# Schematic_Light_Project.net
KiCad netlist of a schematic drawn in EAGLE
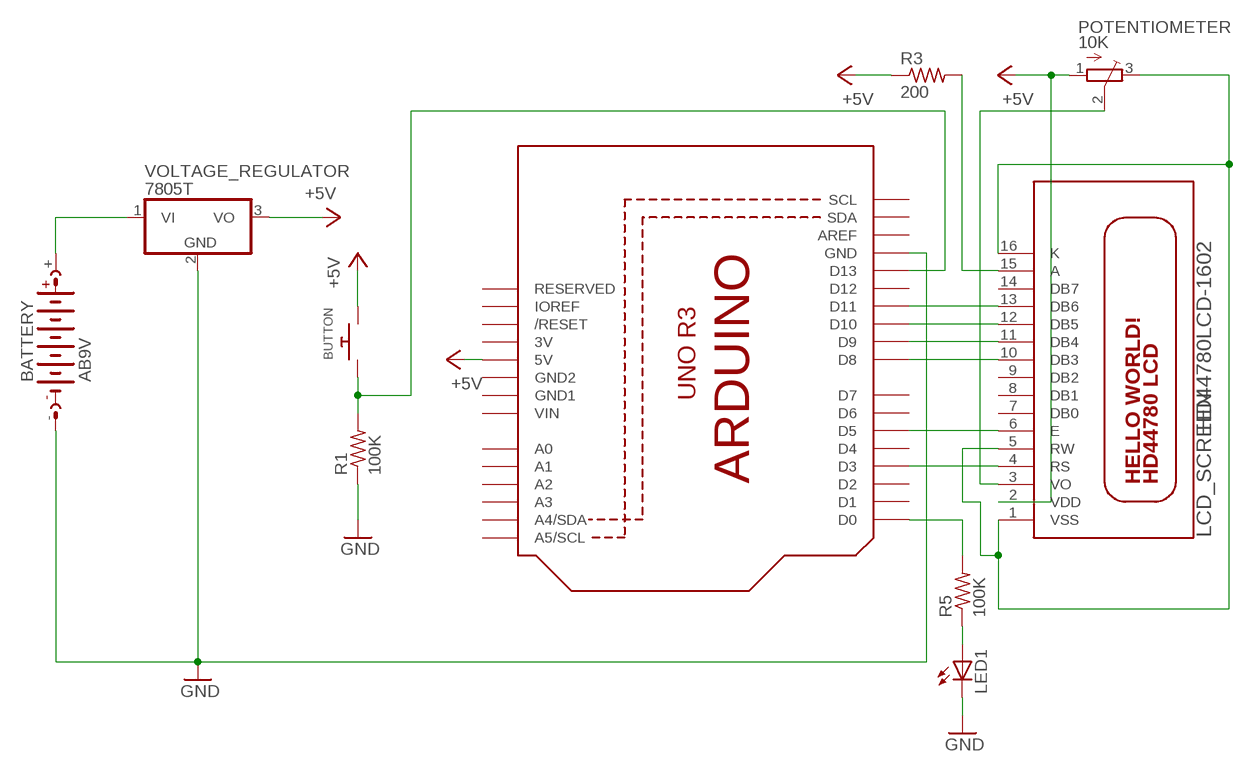
[diagram p0: schematic, sheet 1]

(export (version "E")
  (design (tool "Eeschema 10.0.6"))
  (components
    (comp (ref "ARDUINO")
      (value "ARDUINOR3-DIMENSION")
      (footprint "eagle-import:ARDUINOR3")
      (libsource (lib "eagle-import") (part "ARDUINOR3-DIMENSION"))
    )
    (comp (ref "BATTERY")
      (value "AB9V")
      (footprint "eagle-import:AB9V")
      (libsource (lib "eagle-import") (part "AB9V"))
    )
    (comp (ref "BUTTON")
      (value "SWITCH_PUSHBUTTONSOFTTOUCHSMD_SJ")
      (footprint "eagle-import:PUSHBUTTON_SMD_SJ")
      (libsource (lib "eagle-import") (part "SWITCH_PUSHBUTTONSOFTTOUCHSMD_SJ"))
    )
    (comp (ref "LCD_SCREEN")
      (value "HD44780LCD-1602")
      (footprint "eagle-import:LCD1602")
      (libsource (lib "eagle-import") (part "HD44780LCD-1602"))
    )
    (comp (ref "LED1")
      (value "LED5MM")
      (footprint "eagle-import:LED5MM")
      (libsource (lib "eagle-import") (part "LED5MM"))
    )
    (comp (ref "POTENTIOMETER")
      (value "10K")
      (footprint "eagle-import:TRIM-3386")
      (libsource (lib "eagle-import") (part "TRIMPOT3386"))
    )
    (comp (ref "R1")
      (value "100K")
      (footprint "eagle-import:M0805")
      (libsource (lib "eagle-import") (part "R-US_M0805"))
    )
    (comp (ref "R3")
      (value "200")
      (footprint "eagle-import:M0805")
      (libsource (lib "eagle-import") (part "R-US_M0805"))
    )
    (comp (ref "R5")
      (value "100K")
      (footprint "eagle-import:M0805")
      (libsource (lib "eagle-import") (part "R-US_M0805"))
    )
    (comp (ref "VOLTAGE_REGULATOR")
      (value "7805T")
      (footprint "eagle-import:TO220H")
      (libsource (lib "eagle-import") (part "78T05"))
    )
  )
  (nets
    (net (code "1") (name "+5V") (class "Default")
      (node (ref "ARDUINO") (pin "5V") (pinfunction "5V_5V") (pintype "power_in"))
      (node (ref "BUTTON") (pin "P$2") (pinfunction "P$2_P$2") (pintype "passive"))
      (node (ref "LCD_SCREEN") (pin "2") (pinfunction "VDD_2") (pintype "power_in"))
      (node (ref "POTENTIOMETER") (pin "1") (pinfunction "A_1") (pintype "passive"))
      (node (ref "R3") (pin "1") (pinfunction "1_1") (pintype "passive"))
      (node (ref "VOLTAGE_REGULATOR") (pin "3") (pinfunction "VO_3") (pintype "passive"))
    )
    (net (code "2") (name "/3V") (class "Default")
      (node (ref "ARDUINO") (pin "3V") (pinfunction "3V_3V") (pintype "power_in"))
    )
    (net (code "3") (name "/GND1") (class "Default")
      (node (ref "ARDUINO") (pin "GND1") (pinfunction "GND1_GND1") (pintype "power_in"))
    )
    (net (code "4") (name "/GND2") (class "Default")
      (node (ref "ARDUINO") (pin "GND2") (pinfunction "GND2_GND2") (pintype "power_in"))
    )
    (net (code "5") (name "/VIN") (class "Default")
      (node (ref "ARDUINO") (pin "VIN") (pinfunction "VIN_VIN") (pintype "power_in"))
    )
    (net (code "6") (name "GND") (class "Default")
      (node (ref "ARDUINO") (pin "GND") (pinfunction "GND_GND") (pintype "power_in"))
      (node (ref "BATTERY") (pin "-") (pinfunction "-_-") (pintype "passive"))
      (node (ref "LED1") (pin "K") (pinfunction "C_K") (pintype "passive"))
      (node (ref "R1") (pin "1") (pinfunction "1_1") (pintype "passive"))
      (node (ref "VOLTAGE_REGULATOR") (pin "2") (pinfunction "GND_2") (pintype "passive"))
    )
    (net (code "7") (name "Net-(ARDUINO-PadD0)") (class "Default")
      (node (ref "ARDUINO") (pin "D0") (pinfunction "D0_D0") (pintype "bidirectional"))
      (node (ref "R5") (pin "2") (pinfunction "2_2") (pintype "passive"))
    )
    (net (code "8") (name "Net-(ARDUINO-PadD13)") (class "Default")
      (node (ref "ARDUINO") (pin "D13") (pinfunction "D13_D13") (pintype "bidirectional"))
      (node (ref "BUTTON") (pin "P$1") (pinfunction "P$1_P$1") (pintype "passive"))
      (node (ref "R1") (pin "2") (pinfunction "2_2") (pintype "passive"))
    )
    (net (code "9") (name "Net-(LCD_SCREEN-A)") (class "Default")
      (node (ref "LCD_SCREEN") (pin "15") (pinfunction "A_15") (pintype "input"))
      (node (ref "R3") (pin "2") (pinfunction "2_2") (pintype "passive"))
    )
    (net (code "10") (name "Net-(LCD_SCREEN-DB3)") (class "Default")
      (node (ref "ARDUINO") (pin "D8") (pinfunction "D8_D8") (pintype "bidirectional"))
      (node (ref "LCD_SCREEN") (pin "10") (pinfunction "DB3_10") (pintype "bidirectional"))
    )
    (net (code "11") (name "Net-(LCD_SCREEN-DB4)") (class "Default")
      (node (ref "ARDUINO") (pin "D9") (pinfunction "D9_D9") (pintype "bidirectional"))
      (node (ref "LCD_SCREEN") (pin "11") (pinfunction "DB4_11") (pintype "bidirectional"))
    )
    (net (code "12") (name "Net-(LCD_SCREEN-DB5)") (class "Default")
      (node (ref "ARDUINO") (pin "D10") (pinfunction "D10_D10") (pintype "bidirectional"))
      (node (ref "LCD_SCREEN") (pin "12") (pinfunction "DB5_12") (pintype "bidirectional"))
    )
    (net (code "13") (name "Net-(LCD_SCREEN-DB6)") (class "Default")
      (node (ref "ARDUINO") (pin "D11") (pinfunction "D11_D11") (pintype "bidirectional"))
      (node (ref "LCD_SCREEN") (pin "13") (pinfunction "DB6_13") (pintype "bidirectional"))
    )
    (net (code "14") (name "Net-(LCD_SCREEN-E)") (class "Default")
      (node (ref "ARDUINO") (pin "D5") (pinfunction "D5_D5") (pintype "bidirectional"))
      (node (ref "LCD_SCREEN") (pin "6") (pinfunction "E_6") (pintype "input"))
    )
    (net (code "15") (name "Net-(LCD_SCREEN-K)") (class "Default")
      (node (ref "LCD_SCREEN") (pin "1") (pinfunction "VSS_1") (pintype "power_in"))
      (node (ref "LCD_SCREEN") (pin "16") (pinfunction "K_16") (pintype "input"))
      (node (ref "LCD_SCREEN") (pin "5") (pinfunction "RW_5") (pintype "input"))
      (node (ref "POTENTIOMETER") (pin "3") (pinfunction "E_3") (pintype "passive"))
    )
    (net (code "16") (name "Net-(LCD_SCREEN-RS)") (class "Default")
      (node (ref "ARDUINO") (pin "D3") (pinfunction "D3_D3") (pintype "bidirectional"))
      (node (ref "LCD_SCREEN") (pin "4") (pinfunction "RS_4") (pintype "input"))
    )
    (net (code "17") (name "Net-(LCD_SCREEN-VO)") (class "Default")
      (node (ref "LCD_SCREEN") (pin "3") (pinfunction "VO_3") (pintype "input"))
      (node (ref "POTENTIOMETER") (pin "2") (pinfunction "S_2") (pintype "passive"))
    )
    (net (code "18") (name "Net-(LED1-PadA)") (class "Default")
      (node (ref "LED1") (pin "A") (pinfunction "A_A") (pintype "passive"))
      (node (ref "R5") (pin "1") (pinfunction "1_1") (pintype "passive"))
    )
    (net (code "19") (name "Net-(VOLTAGE_REGULATOR-VI)") (class "Default")
      (node (ref "BATTERY") (pin "+") (pinfunction "+_+") (pintype "passive"))
      (node (ref "VOLTAGE_REGULATOR") (pin "1") (pinfunction "VI_1") (pintype "input"))
    )
    (net (code "20") (name "unconnected-(ARDUINO-A4{slash}SDA-PadA4)") (class "Default")
      (node (ref "ARDUINO") (pin "A4") (pinfunction "A4/SDA_A4") (pintype "bidirectional"))
    )
    (net (code "21") (name "unconnected-(ARDUINO-A5{slash}SCL-PadA5)") (class "Default")
      (node (ref "ARDUINO") (pin "A5") (pinfunction "A5/SCL_A5") (pintype "bidirectional"))
    )
    (net (code "22") (name "unconnected-(ARDUINO-PadA0)") (class "Default")
      (node (ref "ARDUINO") (pin "A0") (pinfunction "A0_A0") (pintype "bidirectional"))
    )
    (net (code "23") (name "unconnected-(ARDUINO-PadA1)") (class "Default")
      (node (ref "ARDUINO") (pin "A1") (pinfunction "A1_A1") (pintype "bidirectional"))
    )
    (net (code "24") (name "unconnected-(ARDUINO-PadA2)") (class "Default")
      (node (ref "ARDUINO") (pin "A2") (pinfunction "A2_A2") (pintype "bidirectional"))
    )
    (net (code "25") (name "unconnected-(ARDUINO-PadA3)") (class "Default")
      (node (ref "ARDUINO") (pin "A3") (pinfunction "A3_A3") (pintype "bidirectional"))
    )
    (net (code "26") (name "unconnected-(ARDUINO-PadAREF)") (class "Default")
      (node (ref "ARDUINO") (pin "AREF") (pinfunction "AREF_AREF") (pintype "bidirectional"))
    )
    (net (code "27") (name "unconnected-(ARDUINO-PadD1)") (class "Default")
      (node (ref "ARDUINO") (pin "D1") (pinfunction "D1_D1") (pintype "bidirectional"))
    )
    (net (code "28") (name "unconnected-(ARDUINO-PadD2)") (class "Default")
      (node (ref "ARDUINO") (pin "D2") (pinfunction "D2_D2") (pintype "bidirectional"))
    )
    (net (code "29") (name "unconnected-(ARDUINO-PadD4)") (class "Default")
      (node (ref "ARDUINO") (pin "D4") (pinfunction "D4_D4") (pintype "bidirectional"))
    )
    (net (code "30") (name "unconnected-(ARDUINO-PadD6)") (class "Default")
      (node (ref "ARDUINO") (pin "D6") (pinfunction "D6_D6") (pintype "bidirectional"))
    )
    (net (code "31") (name "unconnected-(ARDUINO-PadD7)") (class "Default")
      (node (ref "ARDUINO") (pin "D7") (pinfunction "D7_D7") (pintype "bidirectional"))
    )
    (net (code "32") (name "unconnected-(ARDUINO-PadD12)") (class "Default")
      (node (ref "ARDUINO") (pin "D12") (pinfunction "D12_D12") (pintype "bidirectional"))
    )
    (net (code "33") (name "unconnected-(ARDUINO-PadIOREF)") (class "Default")
      (node (ref "ARDUINO") (pin "IOREF") (pinfunction "IOREF_IOREF") (pintype "output"))
    )
    (net (code "34") (name "unconnected-(ARDUINO-PadRESERVED)") (class "Default")
      (node (ref "ARDUINO") (pin "RESERVED") (pinfunction "RESERVED_RESERVED") (pintype "no_connect"))
    )
    (net (code "35") (name "unconnected-(ARDUINO-PadSCL)") (class "Default")
      (node (ref "ARDUINO") (pin "SCL") (pinfunction "SCL_SCL") (pintype "bidirectional"))
    )
    (net (code "36") (name "unconnected-(ARDUINO-PadSDA)") (class "Default")
      (node (ref "ARDUINO") (pin "SDA") (pinfunction "SDA_SDA") (pintype "bidirectional"))
    )
    (net (code "37") (name "unconnected-(ARDUINO-{slash}RESET-PadRESET)") (class "Default")
      (node (ref "ARDUINO") (pin "RESET") (pinfunction "/RESET_RESET") (pintype "bidirectional"))
    )
    (net (code "38") (name "unconnected-(LCD_SCREEN-DB0-Pad7)") (class "Default")
      (node (ref "LCD_SCREEN") (pin "7") (pinfunction "DB0_7") (pintype "bidirectional"))
    )
    (net (code "39") (name "unconnected-(LCD_SCREEN-DB1-Pad8)") (class "Default")
      (node (ref "LCD_SCREEN") (pin "8") (pinfunction "DB1_8") (pintype "bidirectional"))
    )
    (net (code "40") (name "unconnected-(LCD_SCREEN-DB2-Pad9)") (class "Default")
      (node (ref "LCD_SCREEN") (pin "9") (pinfunction "DB2_9") (pintype "bidirectional"))
    )
    (net (code "41") (name "unconnected-(LCD_SCREEN-DB7-Pad14)") (class "Default")
      (node (ref "LCD_SCREEN") (pin "14") (pinfunction "DB7_14") (pintype "bidirectional"))
    )
  )
)
